# IO_V1_1.net
KiCad netlist of a schematic drawn in EAGLE
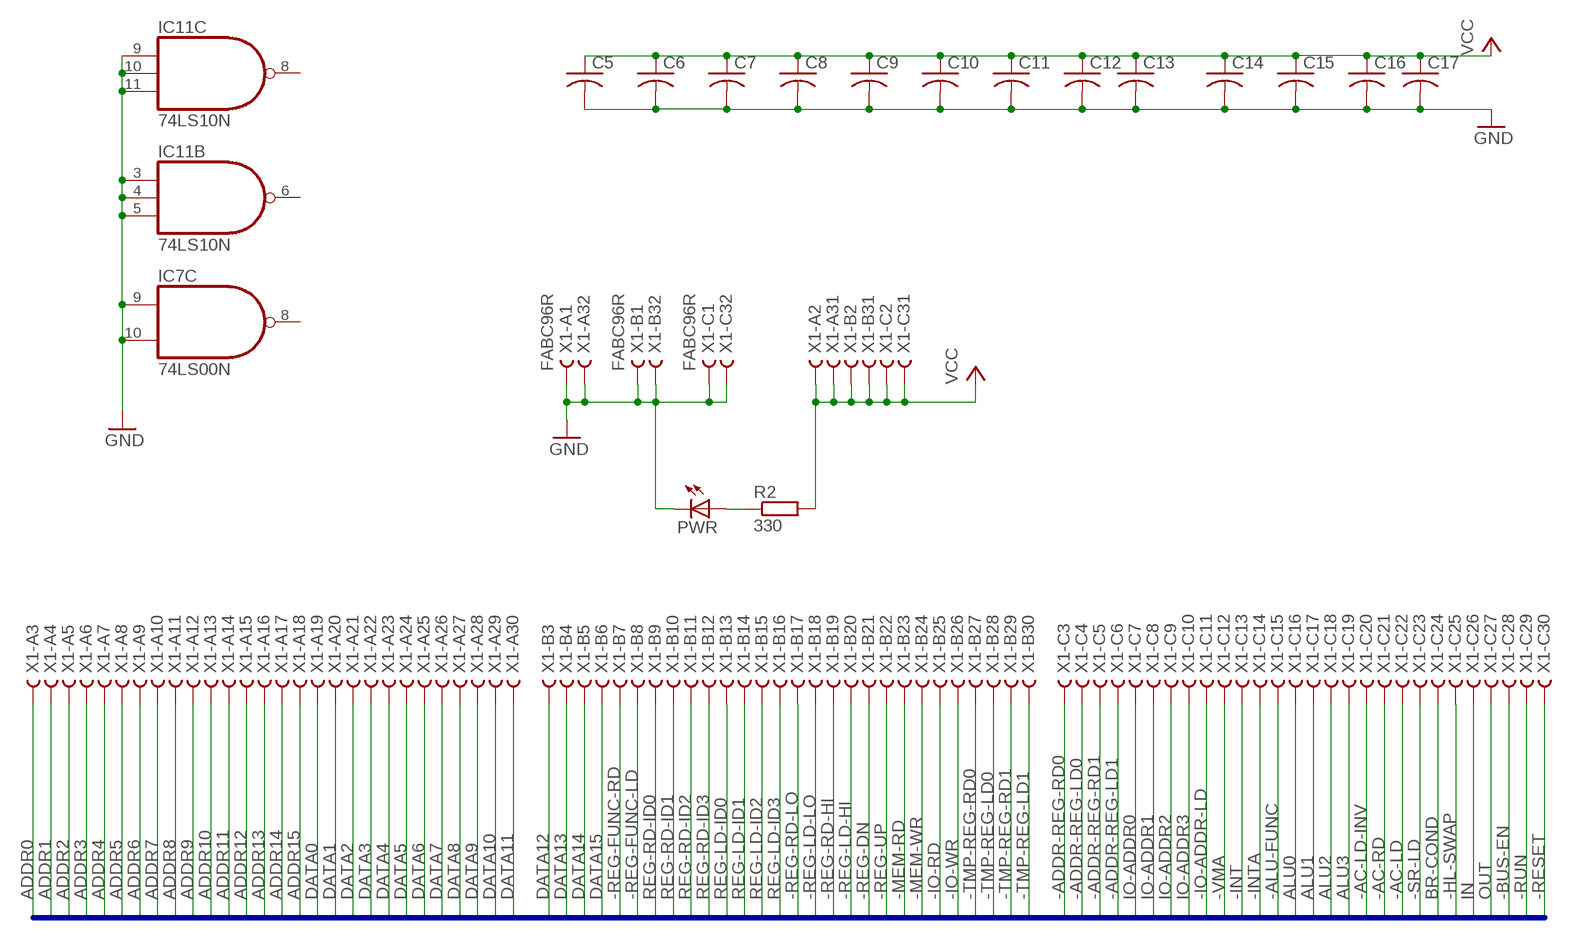
[diagram p0: schematic, sheet 1]
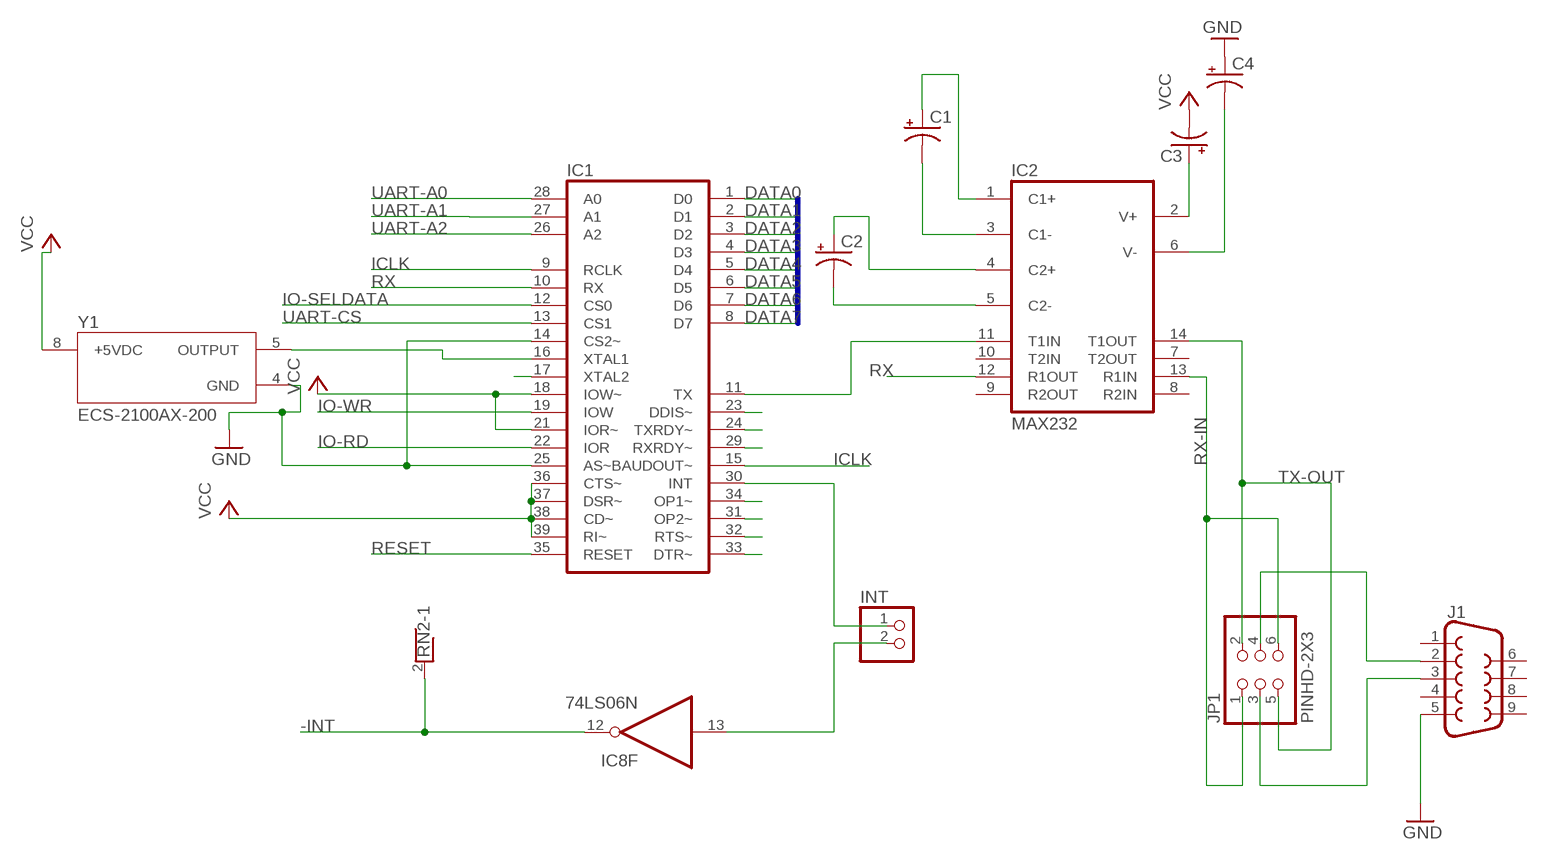
[diagram p1: schematic, sheet 2]
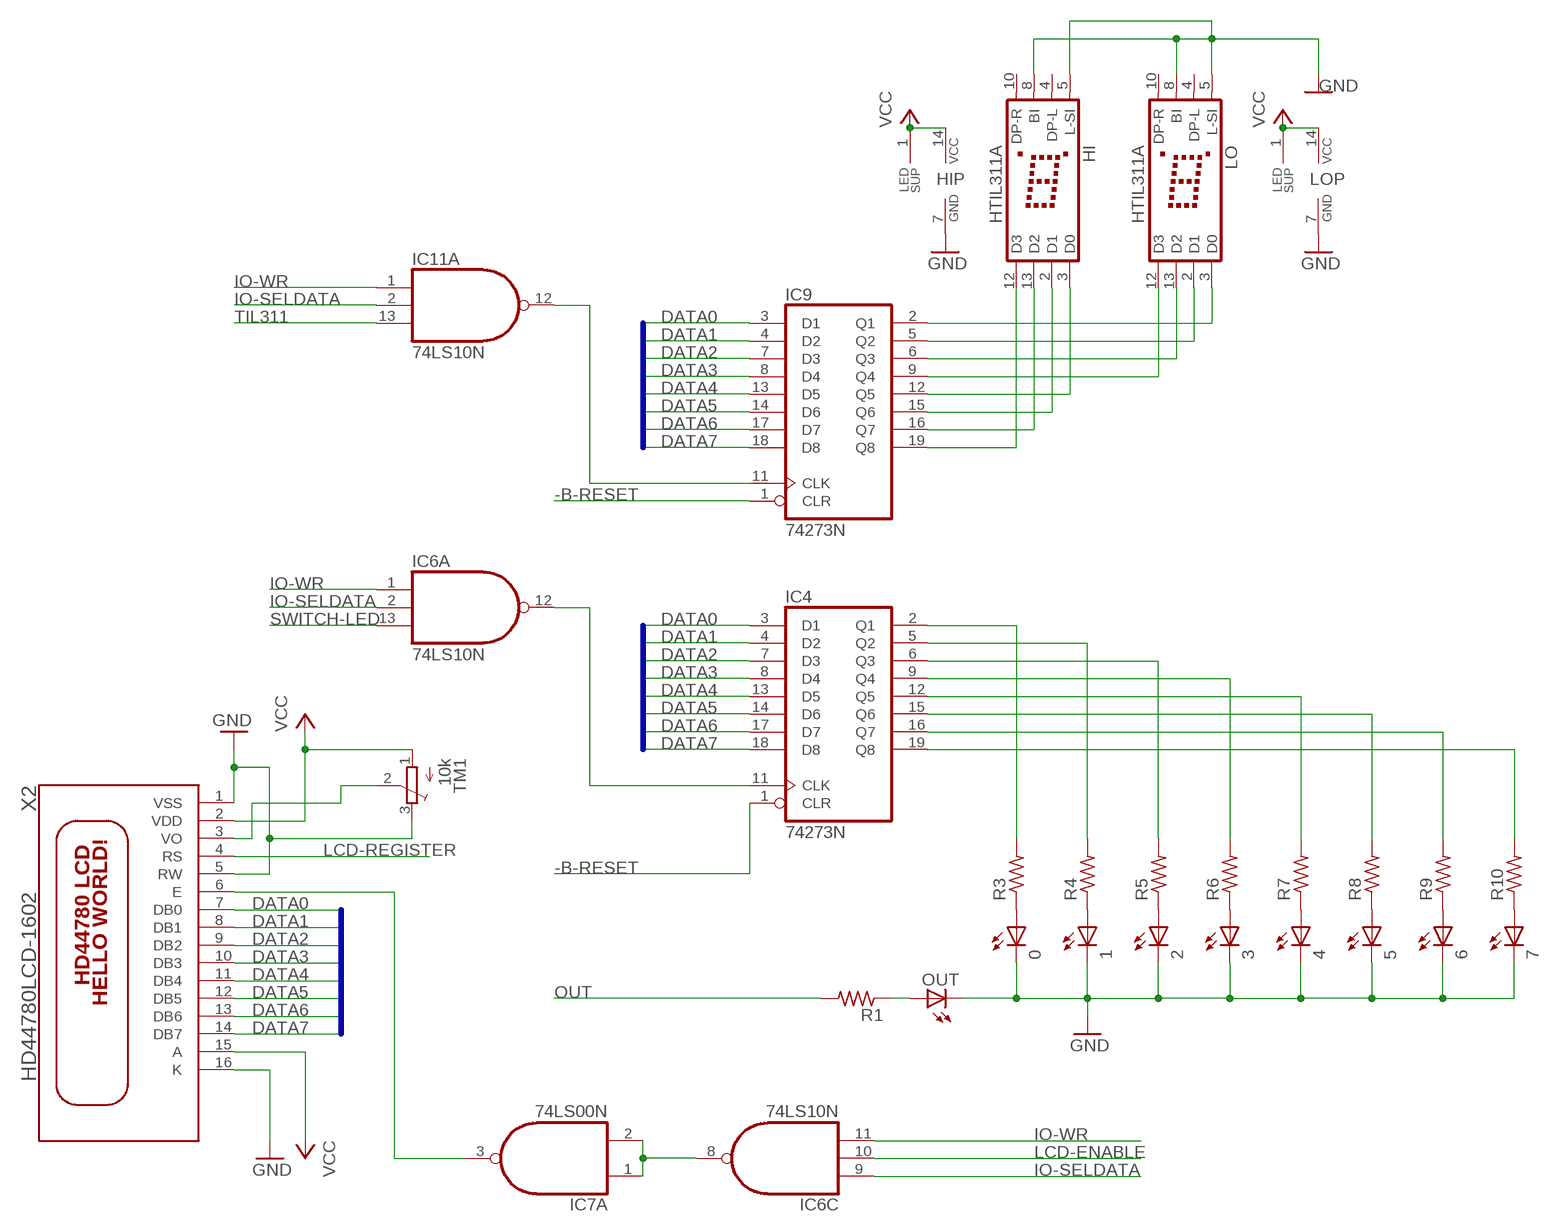
[diagram p2: schematic, sheet 3]
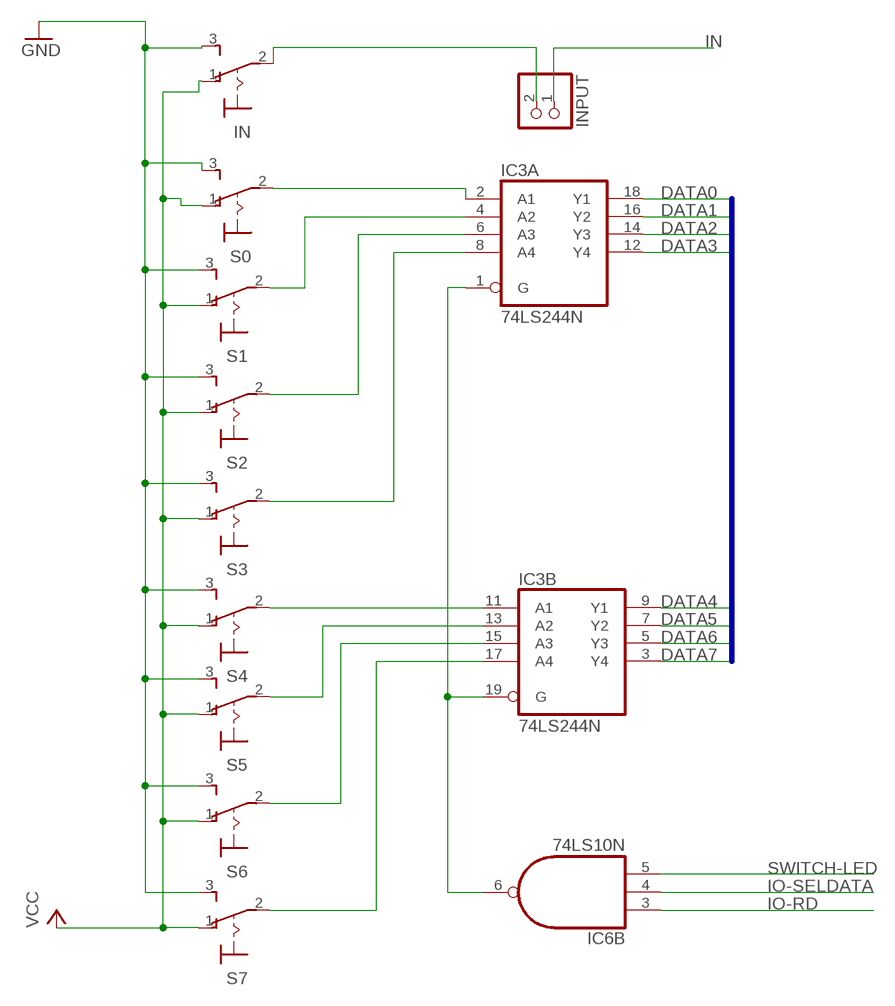
[diagram p3: schematic, sheet 4]
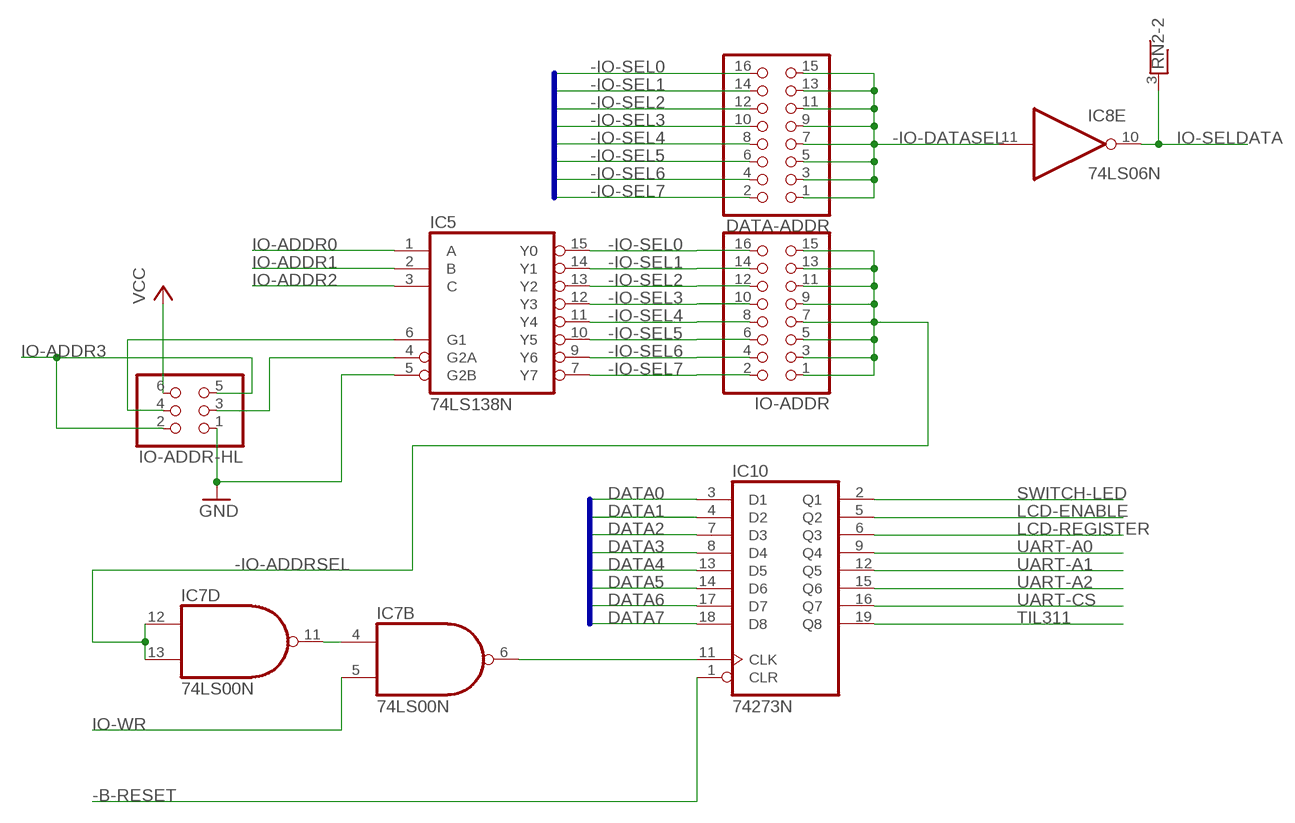
[diagram p4: schematic, sheet 5]
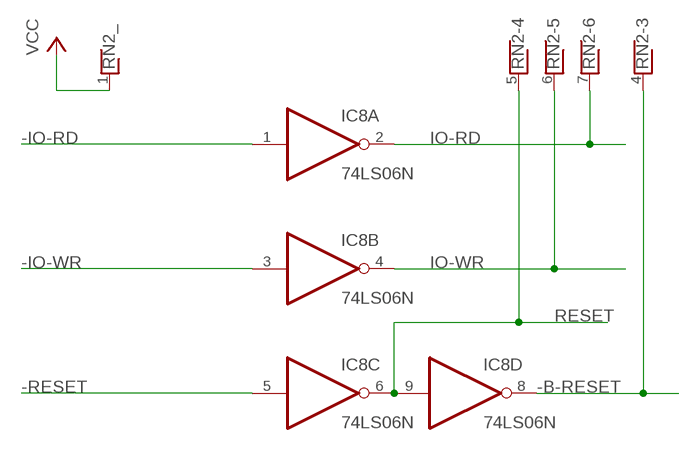
[diagram p5: schematic, sheet 6]

(export (version "E")
  (design (tool "Eeschema 10.0.6"))
  (components
    (comp (ref "C5")
      (value "C-US025-024X044")
      (footprint "eagle-import:C025-024X044")
      (libsource (lib "eagle-import") (part "C-US025-024X044"))
    )
    (comp (ref "C6")
      (value "C-US025-024X044")
      (footprint "eagle-import:C025-024X044")
      (libsource (lib "eagle-import") (part "C-US025-024X044"))
    )
    (comp (ref "C7")
      (value "C-US025-024X044")
      (footprint "eagle-import:C025-024X044")
      (libsource (lib "eagle-import") (part "C-US025-024X044"))
    )
    (comp (ref "C8")
      (value "C-US025-024X044")
      (footprint "eagle-import:C025-024X044")
      (libsource (lib "eagle-import") (part "C-US025-024X044"))
    )
    (comp (ref "C9")
      (value "C-US025-024X044")
      (footprint "eagle-import:C025-024X044")
      (libsource (lib "eagle-import") (part "C-US025-024X044"))
    )
    (comp (ref "C10")
      (value "C-US025-024X044")
      (footprint "eagle-import:C025-024X044")
      (libsource (lib "eagle-import") (part "C-US025-024X044"))
    )
    (comp (ref "C11")
      (value "C-US025-024X044")
      (footprint "eagle-import:C025-024X044")
      (libsource (lib "eagle-import") (part "C-US025-024X044"))
    )
    (comp (ref "C12")
      (value "C-US025-024X044")
      (footprint "eagle-import:C025-024X044")
      (libsource (lib "eagle-import") (part "C-US025-024X044"))
    )
    (comp (ref "C13")
      (value "C-US025-024X044")
      (footprint "eagle-import:C025-024X044")
      (libsource (lib "eagle-import") (part "C-US025-024X044"))
    )
    (comp (ref "C14")
      (value "C-US025-024X044")
      (footprint "eagle-import:C025-024X044")
      (libsource (lib "eagle-import") (part "C-US025-024X044"))
    )
    (comp (ref "C15")
      (value "C-US025-024X044")
      (footprint "eagle-import:C025-024X044")
      (libsource (lib "eagle-import") (part "C-US025-024X044"))
    )
    (comp (ref "C16")
      (value "C-US025-024X044")
      (footprint "eagle-import:C025-024X044")
      (libsource (lib "eagle-import") (part "C-US025-024X044"))
    )
    (comp (ref "C17")
      (value "C-US025-024X044")
      (footprint "eagle-import:C025-024X044")
      (libsource (lib "eagle-import") (part "C-US025-024X044"))
    )
    (comp (ref "IC7")
      (value "74LS00N")
      (footprint "eagle-import:DIL14")
      (libsource (lib "eagle-import") (part "7400NLS"))
    )
    (comp (ref "IC11")
      (value "74LS10N")
      (footprint "eagle-import:DIL14")
      (libsource (lib "eagle-import") (part "7410NLS"))
    )
    (comp (ref "PWR")
      (value "LED5MM")
      (footprint "eagle-import:LED5MM")
      (libsource (lib "eagle-import") (part "led_LED5MM"))
    )
    (comp (ref "R2")
      (value "330")
      (footprint "eagle-import:0207_10")
      (libsource (lib "eagle-import") (part "R0207/10"))
    )
    (comp (ref "X1")
      (value "FABC96R")
      (footprint "eagle-import:FABC96R")
      (libsource (lib "eagle-import") (part "FABC96R"))
    )
    (comp (ref "0")
      (value "LED5MM")
      (footprint "eagle-import:LED5MM")
      (libsource (lib "eagle-import") (part "LED5MM"))
    )
    (comp (ref "1")
      (value "LED5MM")
      (footprint "eagle-import:LED5MM")
      (libsource (lib "eagle-import") (part "LED5MM"))
    )
    (comp (ref "2")
      (value "LED5MM")
      (footprint "eagle-import:LED5MM")
      (libsource (lib "eagle-import") (part "LED5MM"))
    )
    (comp (ref "3")
      (value "LED5MM")
      (footprint "eagle-import:LED5MM")
      (libsource (lib "eagle-import") (part "LED5MM"))
    )
    (comp (ref "4")
      (value "LED5MM")
      (footprint "eagle-import:LED5MM")
      (libsource (lib "eagle-import") (part "LED5MM"))
    )
    (comp (ref "5")
      (value "LED5MM")
      (footprint "eagle-import:LED5MM")
      (libsource (lib "eagle-import") (part "LED5MM"))
    )
    (comp (ref "6")
      (value "LED5MM")
      (footprint "eagle-import:LED5MM")
      (libsource (lib "eagle-import") (part "LED5MM"))
    )
    (comp (ref "7")
      (value "LED5MM")
      (footprint "eagle-import:LED5MM")
      (libsource (lib "eagle-import") (part "LED5MM"))
    )
    (comp (ref "HI")
      (value "HTIL311A")
      (footprint "eagle-import:HTIL311A")
      (libsource (lib "eagle-import") (part "HTIL311A"))
    )
    (comp (ref "IC4")
      (value "74273N")
      (footprint "eagle-import:DIL20")
      (libsource (lib "eagle-import") (part "74273N"))
    )
    (comp (ref "IC6")
      (value "74LS10N")
      (footprint "eagle-import:DIL14")
      (libsource (lib "eagle-import") (part "7410NLS"))
    )
    (comp (ref "IC9")
      (value "74273N")
      (footprint "eagle-import:DIL20")
      (libsource (lib "eagle-import") (part "74273N"))
    )
    (comp (ref "LO")
      (value "HTIL311A")
      (footprint "eagle-import:HTIL311A")
      (libsource (lib "eagle-import") (part "HTIL311A"))
    )
    (comp (ref "OUT")
      (value "LED5MM")
      (footprint "eagle-import:LED5MM")
      (libsource (lib "eagle-import") (part "LED5MM"))
    )
    (comp (ref "R1")
      (value "R-US_0207/10")
      (footprint "eagle-import:0207_10")
      (libsource (lib "eagle-import") (part "R-US_0207/10"))
    )
    (comp (ref "R3")
      (value "R-US_0207/10")
      (footprint "eagle-import:0207_10")
      (libsource (lib "eagle-import") (part "R-US_0207/10"))
    )
    (comp (ref "R4")
      (value "R-US_0207/10")
      (footprint "eagle-import:0207_10")
      (libsource (lib "eagle-import") (part "R-US_0207/10"))
    )
    (comp (ref "R5")
      (value "R-US_0207/10")
      (footprint "eagle-import:0207_10")
      (libsource (lib "eagle-import") (part "R-US_0207/10"))
    )
    (comp (ref "R6")
      (value "R-US_0207/10")
      (footprint "eagle-import:0207_10")
      (libsource (lib "eagle-import") (part "R-US_0207/10"))
    )
    (comp (ref "R7")
      (value "R-US_0207/10")
      (footprint "eagle-import:0207_10")
      (libsource (lib "eagle-import") (part "R-US_0207/10"))
    )
    (comp (ref "R8")
      (value "R-US_0207/10")
      (footprint "eagle-import:0207_10")
      (libsource (lib "eagle-import") (part "R-US_0207/10"))
    )
    (comp (ref "R9")
      (value "R-US_0207/10")
      (footprint "eagle-import:0207_10")
      (libsource (lib "eagle-import") (part "R-US_0207/10"))
    )
    (comp (ref "R10")
      (value "R-US_0207/10")
      (footprint "eagle-import:0207_10")
      (libsource (lib "eagle-import") (part "R-US_0207/10"))
    )
    (comp (ref "TM1")
      (value "10k")
      (footprint "eagle-import:TRIM-3386")
      (libsource (lib "eagle-import") (part "TRIMPOT3386"))
    )
    (comp (ref "X2")
      (value "HD44780LCD-1602")
      (footprint "eagle-import:LCD1602")
      (libsource (lib "eagle-import") (part "HD44780LCD-1602"))
    )
    (comp (ref "DATA-ADDR")
      (value "PINHD-2X8")
      (footprint "eagle-import:2X08")
      (libsource (lib "eagle-import") (part "PINHD-2X8"))
    )
    (comp (ref "IC5")
      (value "74LS138N")
      (footprint "eagle-import:DIL16")
      (libsource (lib "eagle-import") (part "74138NLS"))
    )
    (comp (ref "IC8")
      (value "74LS06N")
      (footprint "eagle-import:DIL14")
      (libsource (lib "eagle-import") (part "7406NLS"))
    )
    (comp (ref "IC10")
      (value "74273N")
      (footprint "eagle-import:DIL20")
      (libsource (lib "eagle-import") (part "74273N"))
    )
    (comp (ref "IO-ADDR")
      (value "PINHD-2X8")
      (footprint "eagle-import:2X08")
      (libsource (lib "eagle-import") (part "PINHD-2X8"))
    )
    (comp (ref "IO-ADDR-HL")
      (value "PINHD-2X3")
      (footprint "eagle-import:2X03")
      (libsource (lib "eagle-import") (part "pinhead_325_PINHD-2X3"))
    )
    (comp (ref "RN2")
      (value "RNX6")
      (footprint "eagle-import:RN-7")
      (libsource (lib "eagle-import") (part "RNX6"))
    )
    (comp (ref "IC3")
      (value "74LS244N")
      (footprint "eagle-import:DIL20")
      (libsource (lib "eagle-import") (part "74xx-us_88_74244NLS"))
    )
    (comp (ref "IN")
      (value "M9040P")
      (footprint "eagle-import:M9040P")
      (libsource (lib "eagle-import") (part "M9040P"))
    )
    (comp (ref "INPUT")
      (value "PINHD-1X2")
      (footprint "eagle-import:1X02")
      (libsource (lib "eagle-import") (part "PINHD-1X2"))
    )
    (comp (ref "S0")
      (value "M9040P")
      (footprint "eagle-import:M9040P")
      (libsource (lib "eagle-import") (part "M9040P"))
    )
    (comp (ref "S1")
      (value "M9040P")
      (footprint "eagle-import:M9040P")
      (libsource (lib "eagle-import") (part "M9040P"))
    )
    (comp (ref "S2")
      (value "M9040P")
      (footprint "eagle-import:M9040P")
      (libsource (lib "eagle-import") (part "M9040P"))
    )
    (comp (ref "S3")
      (value "M9040P")
      (footprint "eagle-import:M9040P")
      (libsource (lib "eagle-import") (part "M9040P"))
    )
    (comp (ref "S4")
      (value "M9040P")
      (footprint "eagle-import:M9040P")
      (libsource (lib "eagle-import") (part "M9040P"))
    )
    (comp (ref "S5")
      (value "M9040P")
      (footprint "eagle-import:M9040P")
      (libsource (lib "eagle-import") (part "M9040P"))
    )
    (comp (ref "S6")
      (value "M9040P")
      (footprint "eagle-import:M9040P")
      (libsource (lib "eagle-import") (part "M9040P"))
    )
    (comp (ref "S7")
      (value "M9040P")
      (footprint "eagle-import:M9040P")
      (libsource (lib "eagle-import") (part "M9040P"))
    )
    (comp (ref "C1")
      (value "CPOL-USE2,5-6E")
      (footprint "eagle-import:E2,5-6E")
      (libsource (lib "eagle-import") (part "CPOL-USE2,5-6E"))
    )
    (comp (ref "C2")
      (value "CPOL-USE2,5-6E")
      (footprint "eagle-import:E2,5-6E")
      (libsource (lib "eagle-import") (part "CPOL-USE2,5-6E"))
    )
    (comp (ref "C3")
      (value "CPOL-USE2,5-6E")
      (footprint "eagle-import:E2,5-6E")
      (libsource (lib "eagle-import") (part "CPOL-USE2,5-6E"))
    )
    (comp (ref "C4")
      (value "CPOL-USE2,5-6E")
      (footprint "eagle-import:E2,5-6E")
      (libsource (lib "eagle-import") (part "CPOL-USE2,5-6E"))
    )
    (comp (ref "IC1")
      (value "XR-16C550P")
      (footprint "eagle-import:DIL40")
      (fields (field (name "MPN") "ST16C450CP40"))
      (libsource (lib "eagle-import") (part "XR-16C550P"))
    )
    (comp (ref "IC2")
      (value "MAX232")
      (footprint "eagle-import:DIL16")
      (fields (field (name "MF") "MAXIM") (field (name "MPN") "MAX232ACPE+"))
      (libsource (lib "eagle-import") (part "MAX232"))
    )
    (comp (ref "INT")
      (value "PINHD-1X2")
      (footprint "eagle-import:1X02")
      (libsource (lib "eagle-import") (part "PINHD-1X2"))
    )
    (comp (ref "J1")
      (value "DB9FEMALE")
      (footprint "eagle-import:DB9")
      (libsource (lib "eagle-import") (part "DB9FEMALE"))
    )
    (comp (ref "JP1")
      (value "PINHD-2X3")
      (footprint "eagle-import:2X03")
      (libsource (lib "eagle-import") (part "PINHD-2X3"))
    )
    (comp (ref "Y1")
      (value "ECS-2100AX-200")
      (footprint "eagle-import:ECS-2100AX-200")
      (fields
        (field (name "DIGIKEY_PART_NUMBER") "X964-ND")
        (field (name "MANUFACTURER") "ECS Inc.")
        (field (name "CREATED_BY") "PCBLayout.com")
      )
      (libsource (lib "eagle-import") (part "ECS-2100AX-200"))
    )
  )
  (nets
    (net (code "1") (name "-AC-LD") (class "Default")
      (node (ref "X1") (pin "C22") (pinfunction "B_C22") (pintype "passive"))
    )
    (net (code "2") (name "-AC-LD-INV") (class "Default")
      (node (ref "X1") (pin "C20") (pinfunction "B_C20") (pintype "passive"))
    )
    (net (code "3") (name "-AC-RD") (class "Default")
      (node (ref "X1") (pin "C21") (pinfunction "B_C21") (pintype "passive"))
    )
    (net (code "4") (name "-ADDR-REG-LD0") (class "Default")
      (node (ref "X1") (pin "C4") (pinfunction "B_C4") (pintype "passive"))
    )
    (net (code "5") (name "-ADDR-REG-LD1") (class "Default")
      (node (ref "X1") (pin "C6") (pinfunction "B_C6") (pintype "passive"))
    )
    (net (code "6") (name "-ADDR-REG-RD0") (class "Default")
      (node (ref "X1") (pin "C3") (pinfunction "B_C3") (pintype "passive"))
    )
    (net (code "7") (name "-ADDR-REG-RD1") (class "Default")
      (node (ref "X1") (pin "C5") (pinfunction "B_C5") (pintype "passive"))
    )
    (net (code "8") (name "-ALU-FUNC") (class "Default")
      (node (ref "X1") (pin "C15") (pinfunction "B_C15") (pintype "passive"))
    )
    (net (code "9") (name "-B-RESET") (class "Default")
      (node (ref "IC10") (pin "1") (pinfunction "CLR_1") (pintype "input"))
      (node (ref "IC4") (pin "1") (pinfunction "CLR_1") (pintype "input"))
      (node (ref "IC8") (pin "8") (pinfunction "O_8") (pintype "open_collector"))
      (node (ref "IC9") (pin "1") (pinfunction "CLR_1") (pintype "input"))
      (node (ref "RN2") (pin "4") (pinfunction "1_4") (pintype "passive"))
    )
    (net (code "10") (name "-BUS-EN") (class "Default")
      (node (ref "X1") (pin "C28") (pinfunction "B_C28") (pintype "passive"))
    )
    (net (code "11") (name "-HL-SWAP") (class "Default")
      (node (ref "X1") (pin "C25") (pinfunction "B_C25") (pintype "passive"))
    )
    (net (code "12") (name "-INT") (class "Default")
      (node (ref "IC8") (pin "12") (pinfunction "O_12") (pintype "open_collector"))
      (node (ref "RN2") (pin "2") (pinfunction "1_2") (pintype "passive"))
      (node (ref "X1") (pin "C13") (pinfunction "B_C13") (pintype "passive"))
    )
    (net (code "13") (name "-INTA") (class "Default")
      (node (ref "X1") (pin "C14") (pinfunction "B_C14") (pintype "passive"))
    )
    (net (code "14") (name "-IO-ADDR-LD") (class "Default")
      (node (ref "X1") (pin "C11") (pinfunction "B_C11") (pintype "passive"))
    )
    (net (code "15") (name "-IO-ADDRSEL") (class "Default")
      (node (ref "IC7") (pin "12") (pinfunction "I0_12") (pintype "input"))
      (node (ref "IC7") (pin "13") (pinfunction "I1_13") (pintype "input"))
      (node (ref "IO-ADDR") (pin "1") (pinfunction "1_1") (pintype "passive"))
      (node (ref "IO-ADDR") (pin "11") (pinfunction "11_11") (pintype "passive"))
      (node (ref "IO-ADDR") (pin "13") (pinfunction "13_13") (pintype "passive"))
      (node (ref "IO-ADDR") (pin "15") (pinfunction "15_15") (pintype "passive"))
      (node (ref "IO-ADDR") (pin "3") (pinfunction "3_3") (pintype "passive"))
      (node (ref "IO-ADDR") (pin "5") (pinfunction "5_5") (pintype "passive"))
      (node (ref "IO-ADDR") (pin "7") (pinfunction "7_7") (pintype "passive"))
      (node (ref "IO-ADDR") (pin "9") (pinfunction "9_9") (pintype "passive"))
    )
    (net (code "16") (name "-IO-DATASEL") (class "Default")
      (node (ref "DATA-ADDR") (pin "1") (pinfunction "1_1") (pintype "passive"))
      (node (ref "DATA-ADDR") (pin "11") (pinfunction "11_11") (pintype "passive"))
      (node (ref "DATA-ADDR") (pin "13") (pinfunction "13_13") (pintype "passive"))
      (node (ref "DATA-ADDR") (pin "15") (pinfunction "15_15") (pintype "passive"))
      (node (ref "DATA-ADDR") (pin "3") (pinfunction "3_3") (pintype "passive"))
      (node (ref "DATA-ADDR") (pin "5") (pinfunction "5_5") (pintype "passive"))
      (node (ref "DATA-ADDR") (pin "7") (pinfunction "7_7") (pintype "passive"))
      (node (ref "DATA-ADDR") (pin "9") (pinfunction "9_9") (pintype "passive"))
      (node (ref "IC8") (pin "11") (pinfunction "I_11") (pintype "input"))
    )
    (net (code "17") (name "-IO-RD") (class "Default")
      (node (ref "IC8") (pin "1") (pinfunction "I_1") (pintype "input"))
      (node (ref "X1") (pin "B25") (pinfunction "B_B25") (pintype "passive"))
    )
    (net (code "18") (name "-IO-SEL0") (class "Default")
      (node (ref "DATA-ADDR") (pin "16") (pinfunction "16_16") (pintype "passive"))
      (node (ref "IC5") (pin "15") (pinfunction "Y0_15") (pintype "output"))
      (node (ref "IO-ADDR") (pin "16") (pinfunction "16_16") (pintype "passive"))
    )
    (net (code "19") (name "-IO-SEL1") (class "Default")
      (node (ref "DATA-ADDR") (pin "14") (pinfunction "14_14") (pintype "passive"))
      (node (ref "IC5") (pin "14") (pinfunction "Y1_14") (pintype "output"))
      (node (ref "IO-ADDR") (pin "14") (pinfunction "14_14") (pintype "passive"))
    )
    (net (code "20") (name "-IO-SEL2") (class "Default")
      (node (ref "DATA-ADDR") (pin "12") (pinfunction "12_12") (pintype "passive"))
      (node (ref "IC5") (pin "13") (pinfunction "Y2_13") (pintype "output"))
      (node (ref "IO-ADDR") (pin "12") (pinfunction "12_12") (pintype "passive"))
    )
    (net (code "21") (name "-IO-SEL3") (class "Default")
      (node (ref "DATA-ADDR") (pin "10") (pinfunction "10_10") (pintype "passive"))
      (node (ref "IC5") (pin "12") (pinfunction "Y3_12") (pintype "output"))
      (node (ref "IO-ADDR") (pin "10") (pinfunction "10_10") (pintype "passive"))
    )
    (net (code "22") (name "-IO-SEL4") (class "Default")
      (node (ref "DATA-ADDR") (pin "8") (pinfunction "8_8") (pintype "passive"))
      (node (ref "IC5") (pin "11") (pinfunction "Y4_11") (pintype "output"))
      (node (ref "IO-ADDR") (pin "8") (pinfunction "8_8") (pintype "passive"))
    )
    (net (code "23") (name "-IO-SEL5") (class "Default")
      (node (ref "DATA-ADDR") (pin "6") (pinfunction "6_6") (pintype "passive"))
      (node (ref "IC5") (pin "10") (pinfunction "Y5_10") (pintype "output"))
      (node (ref "IO-ADDR") (pin "6") (pinfunction "6_6") (pintype "passive"))
    )
    (net (code "24") (name "-IO-SEL6") (class "Default")
      (node (ref "DATA-ADDR") (pin "4") (pinfunction "4_4") (pintype "passive"))
      (node (ref "IC5") (pin "9") (pinfunction "Y6_9") (pintype "output"))
      (node (ref "IO-ADDR") (pin "4") (pinfunction "4_4") (pintype "passive"))
    )
    (net (code "25") (name "-IO-SEL7") (class "Default")
      (node (ref "DATA-ADDR") (pin "2") (pinfunction "2_2") (pintype "passive"))
      (node (ref "IC5") (pin "7") (pinfunction "Y7_7") (pintype "output"))
      (node (ref "IO-ADDR") (pin "2") (pinfunction "2_2") (pintype "passive"))
    )
    (net (code "26") (name "-IO-WR") (class "Default")
      (node (ref "IC8") (pin "3") (pinfunction "I_3") (pintype "input"))
      (node (ref "X1") (pin "B26") (pinfunction "B_B26") (pintype "passive"))
    )
    (net (code "27") (name "-MEM-RD") (class "Default")
      (node (ref "X1") (pin "B23") (pinfunction "B_B23") (pintype "passive"))
    )
    (net (code "28") (name "-MEM-WR") (class "Default")
      (node (ref "X1") (pin "B24") (pinfunction "B_B24") (pintype "passive"))
    )
    (net (code "29") (name "-REG-DN") (class "Default")
      (node (ref "X1") (pin "B21") (pinfunction "B_B21") (pintype "passive"))
    )
    (net (code "30") (name "-REG-FUNC-LD") (class "Default")
      (node (ref "X1") (pin "B8") (pinfunction "B_B8") (pintype "passive"))
    )
    (net (code "31") (name "-REG-FUNC-RD") (class "Default")
      (node (ref "X1") (pin "B7") (pinfunction "B_B7") (pintype "passive"))
    )
    (net (code "32") (name "-REG-LD-HI") (class "Default")
      (node (ref "X1") (pin "B20") (pinfunction "B_B20") (pintype "passive"))
    )
    (net (code "33") (name "-REG-LD-LO") (class "Default")
      (node (ref "X1") (pin "B18") (pinfunction "B_B18") (pintype "passive"))
    )
    (net (code "34") (name "-REG-RD-HI") (class "Default")
      (node (ref "X1") (pin "B19") (pinfunction "B_B19") (pintype "passive"))
    )
    (net (code "35") (name "-REG-RD-LO") (class "Default")
      (node (ref "X1") (pin "B17") (pinfunction "B_B17") (pintype "passive"))
    )
    (net (code "36") (name "-REG-UP") (class "Default")
      (node (ref "X1") (pin "B22") (pinfunction "B_B22") (pintype "passive"))
    )
    (net (code "37") (name "-RESET") (class "Default")
      (node (ref "IC8") (pin "5") (pinfunction "I_5") (pintype "input"))
      (node (ref "X1") (pin "C30") (pinfunction "B_C30") (pintype "passive"))
    )
    (net (code "38") (name "-RUN") (class "Default")
      (node (ref "X1") (pin "C29") (pinfunction "B_C29") (pintype "passive"))
    )
    (net (code "39") (name "-SR-LD") (class "Default")
      (node (ref "X1") (pin "C23") (pinfunction "B_C23") (pintype "passive"))
    )
    (net (code "40") (name "-TMP-REG-LD0") (class "Default")
      (node (ref "X1") (pin "B28") (pinfunction "B_B28") (pintype "passive"))
    )
    (net (code "41") (name "-TMP-REG-LD1") (class "Default")
      (node (ref "X1") (pin "B30") (pinfunction "B_B30") (pintype "passive"))
    )
    (net (code "42") (name "-TMP-REG-RD0") (class "Default")
      (node (ref "X1") (pin "B27") (pinfunction "B_B27") (pintype "passive"))
    )
    (net (code "43") (name "-TMP-REG-RD1") (class "Default")
      (node (ref "X1") (pin "B29") (pinfunction "B_B29") (pintype "passive"))
    )
    (net (code "44") (name "-VMA") (class "Default")
      (node (ref "X1") (pin "C12") (pinfunction "B_C12") (pintype "passive"))
    )
    (net (code "45") (name "ADDR0") (class "Default")
      (node (ref "X1") (pin "A3") (pinfunction "B_A3") (pintype "passive"))
    )
    (net (code "46") (name "ADDR1") (class "Default")
      (node (ref "X1") (pin "A4") (pinfunction "B_A4") (pintype "passive"))
    )
    (net (code "47") (name "ADDR2") (class "Default")
      (node (ref "X1") (pin "A5") (pinfunction "B_A5") (pintype "passive"))
    )
    (net (code "48") (name "ADDR3") (class "Default")
      (node (ref "X1") (pin "A6") (pinfunction "B_A6") (pintype "passive"))
    )
    (net (code "49") (name "ADDR4") (class "Default")
      (node (ref "X1") (pin "A7") (pinfunction "B_A7") (pintype "passive"))
    )
    (net (code "50") (name "ADDR5") (class "Default")
      (node (ref "X1") (pin "A8") (pinfunction "B_A8") (pintype "passive"))
    )
    (net (code "51") (name "ADDR6") (class "Default")
      (node (ref "X1") (pin "A9") (pinfunction "B_A9") (pintype "passive"))
    )
    (net (code "52") (name "ADDR7") (class "Default")
      (node (ref "X1") (pin "A10") (pinfunction "B_A10") (pintype "passive"))
    )
    (net (code "53") (name "ADDR8") (class "Default")
      (node (ref "X1") (pin "A11") (pinfunction "B_A11") (pintype "passive"))
    )
    (net (code "54") (name "ADDR9") (class "Default")
      (node (ref "X1") (pin "A12") (pinfunction "B_A12") (pintype "passive"))
    )
    (net (code "55") (name "ADDR10") (class "Default")
      (node (ref "X1") (pin "A13") (pinfunction "B_A13") (pintype "passive"))
    )
    (net (code "56") (name "ADDR11") (class "Default")
      (node (ref "X1") (pin "A14") (pinfunction "B_A14") (pintype "passive"))
    )
    (net (code "57") (name "ADDR12") (class "Default")
      (node (ref "X1") (pin "A15") (pinfunction "B_A15") (pintype "passive"))
    )
    (net (code "58") (name "ADDR13") (class "Default")
      (node (ref "X1") (pin "A16") (pinfunction "B_A16") (pintype "passive"))
    )
    (net (code "59") (name "ADDR14") (class "Default")
      (node (ref "X1") (pin "A17") (pinfunction "B_A17") (pintype "passive"))
    )
    (net (code "60") (name "ADDR15") (class "Default")
      (node (ref "X1") (pin "A18") (pinfunction "B_A18") (pintype "passive"))
    )
    (net (code "61") (name "ALU0") (class "Default")
      (node (ref "X1") (pin "C16") (pinfunction "B_C16") (pintype "passive"))
    )
    (net (code "62") (name "ALU1") (class "Default")
      (node (ref "X1") (pin "C17") (pinfunction "B_C17") (pintype "passive"))
    )
    (net (code "63") (name "ALU2") (class "Default")
      (node (ref "X1") (pin "C18") (pinfunction "B_C18") (pintype "passive"))
    )
    (net (code "64") (name "ALU3") (class "Default")
      (node (ref "X1") (pin "C19") (pinfunction "B_C19") (pintype "passive"))
    )
    (net (code "65") (name "BR-COND") (class "Default")
      (node (ref "X1") (pin "C24") (pinfunction "B_C24") (pintype "passive"))
    )
    (net (code "66") (name "DATA0") (class "Default")
      (node (ref "IC1") (pin "1") (pinfunction "D0_1") (pintype "bidirectional"))
      (node (ref "IC10") (pin "3") (pinfunction "D1_3") (pintype "input"))
      (node (ref "IC3") (pin "18") (pinfunction "Y1_18") (pintype "tri_state"))
      (node (ref "IC4") (pin "3") (pinfunction "D1_3") (pintype "input"))
      (node (ref "IC9") (pin "3") (pinfunction "D1_3") (pintype "input"))
      (node (ref "X1") (pin "A19") (pinfunction "B_A19") (pintype "passive"))
      (node (ref "X2") (pin "7") (pinfunction "DB0_7") (pintype "bidirectional"))
    )
    (net (code "67") (name "DATA1") (class "Default")
      (node (ref "IC1") (pin "2") (pinfunction "D1_2") (pintype "bidirectional"))
      (node (ref "IC10") (pin "4") (pinfunction "D2_4") (pintype "input"))
      (node (ref "IC3") (pin "16") (pinfunction "Y2_16") (pintype "tri_state"))
      (node (ref "IC4") (pin "4") (pinfunction "D2_4") (pintype "input"))
      (node (ref "IC9") (pin "4") (pinfunction "D2_4") (pintype "input"))
      (node (ref "X1") (pin "A20") (pinfunction "B_A20") (pintype "passive"))
      (node (ref "X2") (pin "8") (pinfunction "DB1_8") (pintype "bidirectional"))
    )
    (net (code "68") (name "DATA2") (class "Default")
      (node (ref "IC1") (pin "3") (pinfunction "D2_3") (pintype "bidirectional"))
      (node (ref "IC10") (pin "7") (pinfunction "D3_7") (pintype "input"))
      (node (ref "IC3") (pin "14") (pinfunction "Y3_14") (pintype "tri_state"))
      (node (ref "IC4") (pin "7") (pinfunction "D3_7") (pintype "input"))
      (node (ref "IC9") (pin "7") (pinfunction "D3_7") (pintype "input"))
      (node (ref "X1") (pin "A21") (pinfunction "B_A21") (pintype "passive"))
      (node (ref "X2") (pin "9") (pinfunction "DB2_9") (pintype "bidirectional"))
    )
    (net (code "69") (name "DATA3") (class "Default")
      (node (ref "IC1") (pin "4") (pinfunction "D3_4") (pintype "bidirectional"))
      (node (ref "IC10") (pin "8") (pinfunction "D4_8") (pintype "input"))
      (node (ref "IC3") (pin "12") (pinfunction "Y4_12") (pintype "tri_state"))
      (node (ref "IC4") (pin "8") (pinfunction "D4_8") (pintype "input"))
      (node (ref "IC9") (pin "8") (pinfunction "D4_8") (pintype "input"))
      (node (ref "X1") (pin "A22") (pinfunction "B_A22") (pintype "passive"))
      (node (ref "X2") (pin "10") (pinfunction "DB3_10") (pintype "bidirectional"))
    )
    (net (code "70") (name "DATA4") (class "Default")
      (node (ref "IC1") (pin "5") (pinfunction "D4_5") (pintype "bidirectional"))
      (node (ref "IC10") (pin "13") (pinfunction "D5_13") (pintype "input"))
      (node (ref "IC3") (pin "9") (pinfunction "Y1_9") (pintype "tri_state"))
      (node (ref "IC4") (pin "13") (pinfunction "D5_13") (pintype "input"))
      (node (ref "IC9") (pin "13") (pinfunction "D5_13") (pintype "input"))
      (node (ref "X1") (pin "A23") (pinfunction "B_A23") (pintype "passive"))
      (node (ref "X2") (pin "11") (pinfunction "DB4_11") (pintype "bidirectional"))
    )
    (net (code "71") (name "DATA5") (class "Default")
      (node (ref "IC1") (pin "6") (pinfunction "D5_6") (pintype "bidirectional"))
      (node (ref "IC10") (pin "14") (pinfunction "D6_14") (pintype "input"))
      (node (ref "IC3") (pin "7") (pinfunction "Y2_7") (pintype "tri_state"))
      (node (ref "IC4") (pin "14") (pinfunction "D6_14") (pintype "input"))
      (node (ref "IC9") (pin "14") (pinfunction "D6_14") (pintype "input"))
      (node (ref "X1") (pin "A24") (pinfunction "B_A24") (pintype "passive"))
      (node (ref "X2") (pin "12") (pinfunction "DB5_12") (pintype "bidirectional"))
    )
    (net (code "72") (name "DATA6") (class "Default")
      (node (ref "IC1") (pin "7") (pinfunction "D6_7") (pintype "bidirectional"))
      (node (ref "IC10") (pin "17") (pinfunction "D7_17") (pintype "input"))
      (node (ref "IC3") (pin "5") (pinfunction "Y3_5") (pintype "tri_state"))
      (node (ref "IC4") (pin "17") (pinfunction "D7_17") (pintype "input"))
      (node (ref "IC9") (pin "17") (pinfunction "D7_17") (pintype "input"))
      (node (ref "X1") (pin "A25") (pinfunction "B_A25") (pintype "passive"))
      (node (ref "X2") (pin "13") (pinfunction "DB6_13") (pintype "bidirectional"))
    )
    (net (code "73") (name "DATA7") (class "Default")
      (node (ref "IC1") (pin "8") (pinfunction "D7_8") (pintype "bidirectional"))
      (node (ref "IC10") (pin "18") (pinfunction "D8_18") (pintype "input"))
      (node (ref "IC3") (pin "3") (pinfunction "Y4_3") (pintype "tri_state"))
      (node (ref "IC4") (pin "18") (pinfunction "D8_18") (pintype "input"))
      (node (ref "IC9") (pin "18") (pinfunction "D8_18") (pintype "input"))
      (node (ref "X1") (pin "A26") (pinfunction "B_A26") (pintype "passive"))
      (node (ref "X2") (pin "14") (pinfunction "DB7_14") (pintype "bidirectional"))
    )
    (net (code "74") (name "DATA8") (class "Default")
      (node (ref "X1") (pin "A27") (pinfunction "B_A27") (pintype "passive"))
    )
    (net (code "75") (name "DATA9") (class "Default")
      (node (ref "X1") (pin "A28") (pinfunction "B_A28") (pintype "passive"))
    )
    (net (code "76") (name "DATA10") (class "Default")
      (node (ref "X1") (pin "A29") (pinfunction "B_A29") (pintype "passive"))
    )
    (net (code "77") (name "DATA11") (class "Default")
      (node (ref "X1") (pin "A30") (pinfunction "B_A30") (pintype "passive"))
    )
    (net (code "78") (name "DATA12") (class "Default")
      (node (ref "X1") (pin "B3") (pinfunction "B_B3") (pintype "passive"))
    )
    (net (code "79") (name "DATA13") (class "Default")
      (node (ref "X1") (pin "B4") (pinfunction "B_B4") (pintype "passive"))
    )
    (net (code "80") (name "DATA14") (class "Default")
      (node (ref "X1") (pin "B5") (pinfunction "B_B5") (pintype "passive"))
    )
    (net (code "81") (name "DATA15") (class "Default")
      (node (ref "X1") (pin "B6") (pinfunction "B_B6") (pintype "passive"))
    )
    (net (code "82") (name "GND") (class "Default")
      (node (ref "0") (pin "K") (pinfunction "C_K") (pintype "passive"))
      (node (ref "1") (pin "K") (pinfunction "C_K") (pintype "passive"))
      (node (ref "2") (pin "K") (pinfunction "C_K") (pintype "passive"))
      (node (ref "3") (pin "K") (pinfunction "C_K") (pintype "passive"))
      (node (ref "4") (pin "K") (pinfunction "C_K") (pintype "passive"))
      (node (ref "5") (pin "K") (pinfunction "C_K") (pintype "passive"))
      (node (ref "6") (pin "K") (pinfunction "C_K") (pintype "passive"))
      (node (ref "7") (pin "K") (pinfunction "C_K") (pintype "passive"))
      (node (ref "C10") (pin "2") (pinfunction "2_2") (pintype "passive"))
      (node (ref "C11") (pin "2") (pinfunction "2_2") (pintype "passive"))
      (node (ref "C12") (pin "2") (pinfunction "2_2") (pintype "passive"))
      (node (ref "C13") (pin "2") (pinfunction "2_2") (pintype "passive"))
      (node (ref "C14") (pin "2") (pinfunction "2_2") (pintype "passive"))
      (node (ref "C15") (pin "2") (pinfunction "2_2") (pintype "passive"))
      (node (ref "C16") (pin "2") (pinfunction "2_2") (pintype "passive"))
      (node (ref "C17") (pin "2") (pinfunction "2_2") (pintype "passive"))
      (node (ref "C4") (pin "+") (pinfunction "+_+") (pintype "passive"))
      (node (ref "C5") (pin "2") (pinfunction "2_2") (pintype "passive"))
      (node (ref "C6") (pin "2") (pinfunction "2_2") (pintype "passive"))
      (node (ref "C7") (pin "2") (pinfunction "2_2") (pintype "passive"))
      (node (ref "C8") (pin "2") (pinfunction "2_2") (pintype "passive"))
      (node (ref "C9") (pin "2") (pinfunction "2_2") (pintype "passive"))
      (node (ref "HI") (pin "5") (pinfunction "L-SI_5") (pintype "input"))
      (node (ref "HI") (pin "7") (pinfunction "GND_7") (pintype "power_in"))
      (node (ref "HI") (pin "8") (pinfunction "BI_8") (pintype "input"))
      (node (ref "IC1") (pin "14") (pinfunction "CS2~{}_14") (pintype "input"))
      (node (ref "IC1") (pin "25") (pinfunction "AS~{}_25") (pintype "input"))
      (node (ref "IC11") (pin "10") (pinfunction "I1_10") (pintype "input"))
      (node (ref "IC11") (pin "11") (pinfunction "I2_11") (pintype "input"))
      (node (ref "IC11") (pin "3") (pinfunction "I0_3") (pintype "input"))
      (node (ref "IC11") (pin "4") (pinfunction "I1_4") (pintype "input"))
      (node (ref "IC11") (pin "5") (pinfunction "I2_5") (pintype "input"))
      (node (ref "IC11") (pin "9") (pinfunction "I0_9") (pintype "input"))
      (node (ref "IC5") (pin "5") (pinfunction "G2B_5") (pintype "input"))
      (node (ref "IC7") (pin "10") (pinfunction "I1_10") (pintype "input"))
      (node (ref "IC7") (pin "9") (pinfunction "I0_9") (pintype "input"))
      (node (ref "IN") (pin "3") (pinfunction "S_3") (pintype "passive"))
      (node (ref "IO-ADDR-HL") (pin "1") (pinfunction "1_1") (pintype "passive"))
      (node (ref "J1") (pin "5") (pinfunction "5_5") (pintype "passive"))
      (node (ref "LO") (pin "5") (pinfunction "L-SI_5") (pintype "input"))
      (node (ref "LO") (pin "7") (pinfunction "GND_7") (pintype "power_in"))
      (node (ref "LO") (pin "8") (pinfunction "BI_8") (pintype "input"))
      (node (ref "OUT") (pin "K") (pinfunction "C_K") (pintype "passive"))
      (node (ref "PWR") (pin "K") (pinfunction "C_K") (pintype "passive"))
      (node (ref "S0") (pin "3") (pinfunction "S_3") (pintype "passive"))
      (node (ref "S1") (pin "3") (pinfunction "S_3") (pintype "passive"))
      (node (ref "S2") (pin "3") (pinfunction "S_3") (pintype "passive"))
      (node (ref "S3") (pin "3") (pinfunction "S_3") (pintype "passive"))
      (node (ref "S4") (pin "3") (pinfunction "S_3") (pintype "passive"))
      (node (ref "S5") (pin "3") (pinfunction "S_3") (pintype "passive"))
      (node (ref "S6") (pin "3") (pinfunction "S_3") (pintype "passive"))
      (node (ref "S7") (pin "3") (pinfunction "S_3") (pintype "passive"))
      (node (ref "TM1") (pin "3") (pinfunction "E_3") (pintype "passive"))
      (node (ref "X1") (pin "A1") (pinfunction "B_A1") (pintype "passive"))
      (node (ref "X1") (pin "A32") (pinfunction "B_A32") (pintype "passive"))
      (node (ref "X1") (pin "B1") (pinfunction "B_B1") (pintype "passive"))
      (node (ref "X1") (pin "B32") (pinfunction "B_B32") (pintype "passive"))
      (node (ref "X1") (pin "C1") (pinfunction "B_C1") (pintype "passive"))
      (node (ref "X1") (pin "C32") (pinfunction "B_C32") (pintype "passive"))
      (node (ref "X2") (pin "1") (pinfunction "VSS_1") (pintype "power_in"))
      (node (ref "X2") (pin "16") (pinfunction "K_16") (pintype "input"))
      (node (ref "X2") (pin "5") (pinfunction "RW_5") (pintype "input"))
      (node (ref "Y1") (pin "4") (pinfunction "GND_4") (pintype "power_in"))
    )
    (net (code "83") (name "ICLK") (class "Default")
      (node (ref "IC1") (pin "15") (pinfunction "BAUDOUT~{}_15") (pintype "output"))
      (node (ref "IC1") (pin "9") (pinfunction "RCLK_9") (pintype "input"))
    )
    (net (code "84") (name "IN") (class "Default")
      (node (ref "INPUT") (pin "1") (pinfunction "1_1") (pintype "passive"))
      (node (ref "X1") (pin "C26") (pinfunction "B_C26") (pintype "passive"))
    )
    (net (code "85") (name "IO-ADDR0") (class "Default")
      (node (ref "IC5") (pin "1") (pinfunction "A_1") (pintype "input"))
      (node (ref "X1") (pin "C7") (pinfunction "B_C7") (pintype "passive"))
    )
    (net (code "86") (name "IO-ADDR1") (class "Default")
      (node (ref "IC5") (pin "2") (pinfunction "B_2") (pintype "input"))
      (node (ref "X1") (pin "C8") (pinfunction "B_C8") (pintype "passive"))
    )
    (net (code "87") (name "IO-ADDR2") (class "Default")
      (node (ref "IC5") (pin "3") (pinfunction "C_3") (pintype "input"))
      (node (ref "X1") (pin "C9") (pinfunction "B_C9") (pintype "passive"))
    )
    (net (code "88") (name "IO-ADDR3") (class "Default")
      (node (ref "IO-ADDR-HL") (pin "2") (pinfunction "2_2") (pintype "passive"))
      (node (ref "IO-ADDR-HL") (pin "5") (pinfunction "5_5") (pintype "passive"))
      (node (ref "X1") (pin "C10") (pinfunction "B_C10") (pintype "passive"))
    )
    (net (code "89") (name "IO-RD") (class "Default")
      (node (ref "IC1") (pin "22") (pinfunction "IOR_22") (pintype "input"))
      (node (ref "IC6") (pin "3") (pinfunction "I0_3") (pintype "input"))
      (node (ref "IC8") (pin "2") (pinfunction "O_2") (pintype "open_collector"))
      (node (ref "RN2") (pin "7") (pinfunction "1_7") (pintype "passive"))
    )
    (net (code "90") (name "IO-SELDATA") (class "Default")
      (node (ref "IC1") (pin "12") (pinfunction "CS0_12") (pintype "input"))
      (node (ref "IC11") (pin "2") (pinfunction "I1_2") (pintype "input"))
      (node (ref "IC6") (pin "2") (pinfunction "I1_2") (pintype "input"))
      (node (ref "IC6") (pin "4") (pinfunction "I1_4") (pintype "input"))
      (node (ref "IC6") (pin "9") (pinfunction "I0_9") (pintype "input"))
      (node (ref "IC8") (pin "10") (pinfunction "O_10") (pintype "open_collector"))
      (node (ref "RN2") (pin "3") (pinfunction "1_3") (pintype "passive"))
    )
    (net (code "91") (name "IO-WR") (class "Default")
      (node (ref "IC1") (pin "19") (pinfunction "IOW_19") (pintype "input"))
      (node (ref "IC11") (pin "1") (pinfunction "I0_1") (pintype "input"))
      (node (ref "IC6") (pin "1") (pinfunction "I0_1") (pintype "input"))
      (node (ref "IC6") (pin "11") (pinfunction "I2_11") (pintype "input"))
      (node (ref "IC7") (pin "5") (pinfunction "I1_5") (pintype "input"))
      (node (ref "IC8") (pin "4") (pinfunction "O_4") (pintype "open_collector"))
      (node (ref "RN2") (pin "6") (pinfunction "1_6") (pintype "passive"))
    )
    (net (code "92") (name "LCD-ENABLE") (class "Default")
      (node (ref "IC10") (pin "5") (pinfunction "Q2_5") (pintype "output"))
      (node (ref "IC6") (pin "10") (pinfunction "I1_10") (pintype "input"))
    )
    (net (code "93") (name "LCD-REGISTER") (class "Default")
      (node (ref "IC10") (pin "6") (pinfunction "Q3_6") (pintype "output"))
      (node (ref "X2") (pin "4") (pinfunction "RS_4") (pintype "input"))
    )
    (net (code "94") (name "Net-(0-PadA)") (class "Default")
      (node (ref "0") (pin "A") (pinfunction "A_A") (pintype "passive"))
      (node (ref "R3") (pin "1") (pinfunction "1_1") (pintype "passive"))
    )
    (net (code "95") (name "Net-(1-PadA)") (class "Default")
      (node (ref "1") (pin "A") (pinfunction "A_A") (pintype "passive"))
      (node (ref "R4") (pin "1") (pinfunction "1_1") (pintype "passive"))
    )
    (net (code "96") (name "Net-(2-PadA)") (class "Default")
      (node (ref "2") (pin "A") (pinfunction "A_A") (pintype "passive"))
      (node (ref "R5") (pin "1") (pinfunction "1_1") (pintype "passive"))
    )
    (net (code "97") (name "Net-(3-PadA)") (class "Default")
      (node (ref "3") (pin "A") (pinfunction "A_A") (pintype "passive"))
      (node (ref "R6") (pin "1") (pinfunction "1_1") (pintype "passive"))
    )
    (net (code "98") (name "Net-(4-PadA)") (class "Default")
      (node (ref "4") (pin "A") (pinfunction "A_A") (pintype "passive"))
      (node (ref "R7") (pin "1") (pinfunction "1_1") (pintype "passive"))
    )
    (net (code "99") (name "Net-(5-PadA)") (class "Default")
      (node (ref "5") (pin "A") (pinfunction "A_A") (pintype "passive"))
      (node (ref "R8") (pin "1") (pinfunction "1_1") (pintype "passive"))
    )
    (net (code "100") (name "Net-(6-PadA)") (class "Default")
      (node (ref "6") (pin "A") (pinfunction "A_A") (pintype "passive"))
      (node (ref "R9") (pin "1") (pinfunction "1_1") (pintype "passive"))
    )
    (net (code "101") (name "Net-(7-PadA)") (class "Default")
      (node (ref "7") (pin "A") (pinfunction "A_A") (pintype "passive"))
      (node (ref "R10") (pin "1") (pinfunction "1_1") (pintype "passive"))
    )
    (net (code "102") (name "Net-(HIA-D0)") (class "Default")
      (node (ref "HI") (pin "3") (pinfunction "D0_3") (pintype "input"))
      (node (ref "IC9") (pin "12") (pinfunction "Q5_12") (pintype "output"))
    )
    (net (code "103") (name "Net-(HIA-D1)") (class "Default")
      (node (ref "HI") (pin "2") (pinfunction "D1_2") (pintype "input"))
      (node (ref "IC9") (pin "15") (pinfunction "Q6_15") (pintype "output"))
    )
    (net (code "104") (name "Net-(HIA-D2)") (class "Default")
      (node (ref "HI") (pin "13") (pinfunction "D2_13") (pintype "input"))
      (node (ref "IC9") (pin "16") (pinfunction "Q7_16") (pintype "output"))
    )
    (net (code "105") (name "Net-(HIA-D3)") (class "Default")
      (node (ref "HI") (pin "12") (pinfunction "D3_12") (pintype "input"))
      (node (ref "IC9") (pin "19") (pinfunction "Q8_19") (pintype "output"))
    )
    (net (code "106") (name "Net-(IC1A-INT)") (class "Default")
      (node (ref "IC1") (pin "30") (pinfunction "INT_30") (pintype "output"))
      (node (ref "INT") (pin "1") (pinfunction "1_1") (pintype "passive"))
    )
    (net (code "107") (name "Net-(IC1A-TX)") (class "Default")
      (node (ref "IC1") (pin "11") (pinfunction "TX_11") (pintype "output"))
      (node (ref "IC2") (pin "11") (pinfunction "T1IN_11") (pintype "input"))
    )
    (net (code "108") (name "Net-(IC1A-XTAL1)") (class "Default")
      (node (ref "IC1") (pin "16") (pinfunction "XTAL1_16") (pintype "input"))
      (node (ref "Y1") (pin "5") (pinfunction "OUTPUT_5") (pintype "output"))
    )
    (net (code "109") (name "Net-(IC2A-C1+)") (class "Default")
      (node (ref "C1") (pin "+") (pinfunction "+_+") (pintype "passive"))
      (node (ref "IC2") (pin "1") (pinfunction "C1+_1") (pintype "bidirectional"))
    )
    (net (code "110") (name "Net-(IC2A-C1-)") (class "Default")
      (node (ref "C1") (pin "-") (pinfunction "-_-") (pintype "passive"))
      (node (ref "IC2") (pin "3") (pinfunction "C1-_3") (pintype "bidirectional"))
    )
    (net (code "111") (name "Net-(IC2A-C2+)") (class "Default")
      (node (ref "C2") (pin "+") (pinfunction "+_+") (pintype "passive"))
      (node (ref "IC2") (pin "4") (pinfunction "C2+_4") (pintype "bidirectional"))
    )
    (net (code "112") (name "Net-(IC2A-C2-)") (class "Default")
      (node (ref "C2") (pin "-") (pinfunction "-_-") (pintype "passive"))
      (node (ref "IC2") (pin "5") (pinfunction "C2-_5") (pintype "bidirectional"))
    )
    (net (code "113") (name "Net-(IC2A-V+)") (class "Default")
      (node (ref "C3") (pin "+") (pinfunction "+_+") (pintype "passive"))
      (node (ref "IC2") (pin "2") (pinfunction "V+_2") (pintype "bidirectional"))
    )
    (net (code "114") (name "Net-(IC2A-V-)") (class "Default")
      (node (ref "C4") (pin "-") (pinfunction "-_-") (pintype "passive"))
      (node (ref "IC2") (pin "6") (pinfunction "V-_6") (pintype "bidirectional"))
    )
    (net (code "115") (name "Net-(IC3A-A1)") (class "Default")
      (node (ref "IC3") (pin "2") (pinfunction "A1_2") (pintype "input"))
      (node (ref "S0") (pin "2") (pinfunction "P_2") (pintype "passive"))
    )
    (net (code "116") (name "Net-(IC3A-A2)") (class "Default")
      (node (ref "IC3") (pin "4") (pinfunction "A2_4") (pintype "input"))
      (node (ref "S1") (pin "2") (pinfunction "P_2") (pintype "passive"))
    )
    (net (code "117") (name "Net-(IC3A-A3)") (class "Default")
      (node (ref "IC3") (pin "6") (pinfunction "A3_6") (pintype "input"))
      (node (ref "S2") (pin "2") (pinfunction "P_2") (pintype "passive"))
    )
    (net (code "118") (name "Net-(IC3A-A4)") (class "Default")
      (node (ref "IC3") (pin "8") (pinfunction "A4_8") (pintype "input"))
      (node (ref "S3") (pin "2") (pinfunction "P_2") (pintype "passive"))
    )
    (net (code "119") (name "Net-(IC3A-G)") (class "Default")
      (node (ref "IC3") (pin "1") (pinfunction "G_1") (pintype "input"))
      (node (ref "IC3") (pin "19") (pinfunction "G_19") (pintype "input"))
      (node (ref "IC6") (pin "6") (pinfunction "O_6") (pintype "output"))
    )
    (net (code "120") (name "Net-(IC3B-A1)") (class "Default")
      (node (ref "IC3") (pin "11") (pinfunction "A1_11") (pintype "input"))
      (node (ref "S4") (pin "2") (pinfunction "P_2") (pintype "passive"))
    )
    (net (code "121") (name "Net-(IC3B-A2)") (class "Default")
      (node (ref "IC3") (pin "13") (pinfunction "A2_13") (pintype "input"))
      (node (ref "S5") (pin "2") (pinfunction "P_2") (pintype "passive"))
    )
    (net (code "122") (name "Net-(IC3B-A3)") (class "Default")
      (node (ref "IC3") (pin "15") (pinfunction "A3_15") (pintype "input"))
      (node (ref "S6") (pin "2") (pinfunction "P_2") (pintype "passive"))
    )
    (net (code "123") (name "Net-(IC3B-A4)") (class "Default")
      (node (ref "IC3") (pin "17") (pinfunction "A4_17") (pintype "input"))
      (node (ref "S7") (pin "2") (pinfunction "P_2") (pintype "passive"))
    )
    (net (code "124") (name "Net-(IC4A-CLK)") (class "Default")
      (node (ref "IC4") (pin "11") (pinfunction "CLK_11") (pintype "input"))
      (node (ref "IC6") (pin "12") (pinfunction "O_12") (pintype "output"))
    )
    (net (code "125") (name "Net-(IC4A-Q1)") (class "Default")
      (node (ref "IC4") (pin "2") (pinfunction "Q1_2") (pintype "output"))
      (node (ref "R3") (pin "2") (pinfunction "2_2") (pintype "passive"))
    )
    (net (code "126") (name "Net-(IC4A-Q2)") (class "Default")
      (node (ref "IC4") (pin "5") (pinfunction "Q2_5") (pintype "output"))
      (node (ref "R4") (pin "2") (pinfunction "2_2") (pintype "passive"))
    )
    (net (code "127") (name "Net-(IC4A-Q3)") (class "Default")
      (node (ref "IC4") (pin "6") (pinfunction "Q3_6") (pintype "output"))
      (node (ref "R5") (pin "2") (pinfunction "2_2") (pintype "passive"))
    )
    (net (code "128") (name "Net-(IC4A-Q4)") (class "Default")
      (node (ref "IC4") (pin "9") (pinfunction "Q4_9") (pintype "output"))
      (node (ref "R6") (pin "2") (pinfunction "2_2") (pintype "passive"))
    )
    (net (code "129") (name "Net-(IC4A-Q5)") (class "Default")
      (node (ref "IC4") (pin "12") (pinfunction "Q5_12") (pintype "output"))
      (node (ref "R7") (pin "2") (pinfunction "2_2") (pintype "passive"))
    )
    (net (code "130") (name "Net-(IC4A-Q6)") (class "Default")
      (node (ref "IC4") (pin "15") (pinfunction "Q6_15") (pintype "output"))
      (node (ref "R8") (pin "2") (pinfunction "2_2") (pintype "passive"))
    )
    (net (code "131") (name "Net-(IC4A-Q7)") (class "Default")
      (node (ref "IC4") (pin "16") (pinfunction "Q7_16") (pintype "output"))
      (node (ref "R9") (pin "2") (pinfunction "2_2") (pintype "passive"))
    )
    (net (code "132") (name "Net-(IC4A-Q8)") (class "Default")
      (node (ref "IC4") (pin "19") (pinfunction "Q8_19") (pintype "output"))
      (node (ref "R10") (pin "2") (pinfunction "2_2") (pintype "passive"))
    )
    (net (code "133") (name "Net-(IC5A-G1)") (class "Default")
      (node (ref "IC5") (pin "6") (pinfunction "G1_6") (pintype "input"))
      (node (ref "IO-ADDR-HL") (pin "4") (pinfunction "4_4") (pintype "passive"))
    )
    (net (code "134") (name "Net-(IC5A-G2A)") (class "Default")
      (node (ref "IC5") (pin "4") (pinfunction "G2A_4") (pintype "input"))
      (node (ref "IO-ADDR-HL") (pin "3") (pinfunction "3_3") (pintype "passive"))
    )
    (net (code "135") (name "Net-(IC6C-O)") (class "Default")
      (node (ref "IC6") (pin "8") (pinfunction "O_8") (pintype "output"))
      (node (ref "IC7") (pin "1") (pinfunction "I0_1") (pintype "input"))
      (node (ref "IC7") (pin "2") (pinfunction "I1_2") (pintype "input"))
    )
    (net (code "136") (name "Net-(IC7A-O)") (class "Default")
      (node (ref "IC7") (pin "3") (pinfunction "O_3") (pintype "output"))
      (node (ref "X2") (pin "6") (pinfunction "E_6") (pintype "input"))
    )
    (net (code "137") (name "Net-(IC7B-I0)") (class "Default")
      (node (ref "IC7") (pin "11") (pinfunction "O_11") (pintype "output"))
      (node (ref "IC7") (pin "4") (pinfunction "I0_4") (pintype "input"))
    )
    (net (code "138") (name "Net-(IC8F-I)") (class "Default")
      (node (ref "IC8") (pin "13") (pinfunction "I_13") (pintype "input"))
      (node (ref "INT") (pin "2") (pinfunction "2_2") (pintype "passive"))
    )
    (net (code "139") (name "Net-(IC9A-Q1)") (class "Default")
      (node (ref "IC9") (pin "2") (pinfunction "Q1_2") (pintype "output"))
      (node (ref "LO") (pin "3") (pinfunction "D0_3") (pintype "input"))
    )
    (net (code "140") (name "Net-(IC9A-Q2)") (class "Default")
      (node (ref "IC9") (pin "5") (pinfunction "Q2_5") (pintype "output"))
      (node (ref "LO") (pin "2") (pinfunction "D1_2") (pintype "input"))
    )
    (net (code "141") (name "Net-(IC9A-Q3)") (class "Default")
      (node (ref "IC9") (pin "6") (pinfunction "Q3_6") (pintype "output"))
      (node (ref "LO") (pin "13") (pinfunction "D2_13") (pintype "input"))
    )
    (net (code "142") (name "Net-(IC9A-Q4)") (class "Default")
      (node (ref "IC9") (pin "9") (pinfunction "Q4_9") (pintype "output"))
      (node (ref "LO") (pin "12") (pinfunction "D3_12") (pintype "input"))
    )
    (net (code "143") (name "Net-(IC10A-CLK)") (class "Default")
      (node (ref "IC10") (pin "11") (pinfunction "CLK_11") (pintype "input"))
      (node (ref "IC7") (pin "6") (pinfunction "O_6") (pintype "output"))
    )
    (net (code "144") (name "Net-(IC11A-O)") (class "Default")
      (node (ref "IC11") (pin "12") (pinfunction "O_12") (pintype "output"))
      (node (ref "IC9") (pin "11") (pinfunction "CLK_11") (pintype "input"))
    )
    (net (code "145") (name "Net-(IN-P)") (class "Default")
      (node (ref "IN") (pin "2") (pinfunction "P_2") (pintype "passive"))
      (node (ref "INPUT") (pin "2") (pinfunction "2_2") (pintype "passive"))
    )
    (net (code "146") (name "Net-(J1-Pad2)") (class "Default")
      (node (ref "J1") (pin "2") (pinfunction "2_2") (pintype "passive"))
      (node (ref "JP1") (pin "4") (pinfunction "4_4") (pintype "passive"))
    )
    (net (code "147") (name "Net-(J1-Pad3)") (class "Default")
      (node (ref "J1") (pin "3") (pinfunction "3_3") (pintype "passive"))
      (node (ref "JP1") (pin "3") (pinfunction "3_3") (pintype "passive"))
    )
    (net (code "148") (name "Net-(OUT-PadA)") (class "Default")
      (node (ref "OUT") (pin "A") (pinfunction "A_A") (pintype "passive"))
      (node (ref "R1") (pin "1") (pinfunction "1_1") (pintype "passive"))
    )
    (net (code "149") (name "Net-(PWR-PadA)") (class "Default")
      (node (ref "PWR") (pin "A") (pinfunction "A_A") (pintype "passive"))
      (node (ref "R2") (pin "1") (pinfunction "1_1") (pintype "passive"))
    )
    (net (code "150") (name "Net-(TM1-S)") (class "Default")
      (node (ref "TM1") (pin "2") (pinfunction "S_2") (pintype "passive"))
      (node (ref "X2") (pin "3") (pinfunction "VO_3") (pintype "input"))
    )
    (net (code "151") (name "OUT") (class "Default")
      (node (ref "R1") (pin "2") (pinfunction "2_2") (pintype "passive"))
      (node (ref "X1") (pin "C27") (pinfunction "B_C27") (pintype "passive"))
    )
    (net (code "152") (name "REG-LD-ID0") (class "Default")
      (node (ref "X1") (pin "B13") (pinfunction "B_B13") (pintype "passive"))
    )
    (net (code "153") (name "REG-LD-ID1") (class "Default")
      (node (ref "X1") (pin "B14") (pinfunction "B_B14") (pintype "passive"))
    )
    (net (code "154") (name "REG-LD-ID2") (class "Default")
      (node (ref "X1") (pin "B15") (pinfunction "B_B15") (pintype "passive"))
    )
    (net (code "155") (name "REG-LD-ID3") (class "Default")
      (node (ref "X1") (pin "B16") (pinfunction "B_B16") (pintype "passive"))
    )
    (net (code "156") (name "REG-RD-ID0") (class "Default")
      (node (ref "X1") (pin "B9") (pinfunction "B_B9") (pintype "passive"))
    )
    (net (code "157") (name "REG-RD-ID1") (class "Default")
      (node (ref "X1") (pin "B10") (pinfunction "B_B10") (pintype "passive"))
    )
    (net (code "158") (name "REG-RD-ID2") (class "Default")
      (node (ref "X1") (pin "B11") (pinfunction "B_B11") (pintype "passive"))
    )
    (net (code "159") (name "REG-RD-ID3") (class "Default")
      (node (ref "X1") (pin "B12") (pinfunction "B_B12") (pintype "passive"))
    )
    (net (code "160") (name "RESET") (class "Default")
      (node (ref "IC1") (pin "35") (pinfunction "RESET_35") (pintype "input"))
      (node (ref "IC8") (pin "6") (pinfunction "O_6") (pintype "open_collector"))
      (node (ref "IC8") (pin "9") (pinfunction "I_9") (pintype "input"))
      (node (ref "RN2") (pin "5") (pinfunction "1_5") (pintype "passive"))
    )
    (net (code "161") (name "RX") (class "Default")
      (node (ref "IC1") (pin "10") (pinfunction "RX_10") (pintype "input"))
      (node (ref "IC2") (pin "12") (pinfunction "R1OUT_12") (pintype "output"))
    )
    (net (code "162") (name "RX-IN") (class "Default")
      (node (ref "IC2") (pin "13") (pinfunction "R1IN_13") (pintype "input"))
      (node (ref "JP1") (pin "1") (pinfunction "1_1") (pintype "passive"))
      (node (ref "JP1") (pin "6") (pinfunction "6_6") (pintype "passive"))
    )
    (net (code "163") (name "SWITCH-LED") (class "Default")
      (node (ref "IC10") (pin "2") (pinfunction "Q1_2") (pintype "output"))
      (node (ref "IC6") (pin "13") (pinfunction "I2_13") (pintype "input"))
      (node (ref "IC6") (pin "5") (pinfunction "I2_5") (pintype "input"))
    )
    (net (code "164") (name "TIL311") (class "Default")
      (node (ref "IC10") (pin "19") (pinfunction "Q8_19") (pintype "output"))
      (node (ref "IC11") (pin "13") (pinfunction "I2_13") (pintype "input"))
    )
    (net (code "165") (name "TX-OUT") (class "Default")
      (node (ref "IC2") (pin "14") (pinfunction "T1OUT_14") (pintype "output"))
      (node (ref "JP1") (pin "2") (pinfunction "2_2") (pintype "passive"))
      (node (ref "JP1") (pin "5") (pinfunction "5_5") (pintype "passive"))
    )
    (net (code "166") (name "UART-A0") (class "Default")
      (node (ref "IC1") (pin "28") (pinfunction "A0_28") (pintype "input"))
      (node (ref "IC10") (pin "9") (pinfunction "Q4_9") (pintype "output"))
    )
    (net (code "167") (name "UART-A1") (class "Default")
      (node (ref "IC1") (pin "27") (pinfunction "A1_27") (pintype "input"))
      (node (ref "IC10") (pin "12") (pinfunction "Q5_12") (pintype "output"))
    )
    (net (code "168") (name "UART-A2") (class "Default")
      (node (ref "IC1") (pin "26") (pinfunction "A2_26") (pintype "input"))
      (node (ref "IC10") (pin "15") (pinfunction "Q6_15") (pintype "output"))
    )
    (net (code "169") (name "UART-CS") (class "Default")
      (node (ref "IC1") (pin "13") (pinfunction "CS1_13") (pintype "input"))
      (node (ref "IC10") (pin "16") (pinfunction "Q7_16") (pintype "output"))
    )
    (net (code "170") (name "VCC") (class "Default")
      (node (ref "C10") (pin "1") (pinfunction "1_1") (pintype "passive"))
      (node (ref "C11") (pin "1") (pinfunction "1_1") (pintype "passive"))
      (node (ref "C12") (pin "1") (pinfunction "1_1") (pintype "passive"))
      (node (ref "C13") (pin "1") (pinfunction "1_1") (pintype "passive"))
      (node (ref "C14") (pin "1") (pinfunction "1_1") (pintype "passive"))
      (node (ref "C15") (pin "1") (pinfunction "1_1") (pintype "passive"))
      (node (ref "C16") (pin "1") (pinfunction "1_1") (pintype "passive"))
      (node (ref "C17") (pin "1") (pinfunction "1_1") (pintype "passive"))
      (node (ref "C3") (pin "-") (pinfunction "-_-") (pintype "passive"))
      (node (ref "C5") (pin "1") (pinfunction "1_1") (pintype "passive"))
      (node (ref "C6") (pin "1") (pinfunction "1_1") (pintype "passive"))
      (node (ref "C7") (pin "1") (pinfunction "1_1") (pintype "passive"))
      (node (ref "C8") (pin "1") (pinfunction "1_1") (pintype "passive"))
      (node (ref "C9") (pin "1") (pinfunction "1_1") (pintype "passive"))
      (node (ref "HI") (pin "1") (pinfunction "LEDSUP_1") (pintype "input"))
      (node (ref "HI") (pin "14") (pinfunction "VCC_14") (pintype "power_in"))
      (node (ref "IC1") (pin "18") (pinfunction "IOW~{}_18") (pintype "input"))
      (node (ref "IC1") (pin "21") (pinfunction "IOR~{}_21") (pintype "input"))
      (node (ref "IC1") (pin "36") (pinfunction "CTS~{}_36") (pintype "input"))
      (node (ref "IC1") (pin "37") (pinfunction "DSR~{}_37") (pintype "input"))
      (node (ref "IC1") (pin "38") (pinfunction "CD~{}_38") (pintype "input"))
      (node (ref "IC1") (pin "39") (pinfunction "RI~{}_39") (pintype "input"))
      (node (ref "IN") (pin "1") (pinfunction "O_1") (pintype "passive"))
      (node (ref "IO-ADDR-HL") (pin "6") (pinfunction "6_6") (pintype "passive"))
      (node (ref "LO") (pin "1") (pinfunction "LEDSUP_1") (pintype "input"))
      (node (ref "LO") (pin "14") (pinfunction "VCC_14") (pintype "power_in"))
      (node (ref "R2") (pin "2") (pinfunction "2_2") (pintype "passive"))
      (node (ref "RN2") (pin "1") (pinfunction "1_1") (pintype "passive"))
      (node (ref "S0") (pin "1") (pinfunction "O_1") (pintype "passive"))
      (node (ref "S1") (pin "1") (pinfunction "O_1") (pintype "passive"))
      (node (ref "S2") (pin "1") (pinfunction "O_1") (pintype "passive"))
      (node (ref "S3") (pin "1") (pinfunction "O_1") (pintype "passive"))
      (node (ref "S4") (pin "1") (pinfunction "O_1") (pintype "passive"))
      (node (ref "S5") (pin "1") (pinfunction "O_1") (pintype "passive"))
      (node (ref "S6") (pin "1") (pinfunction "O_1") (pintype "passive"))
      (node (ref "S7") (pin "1") (pinfunction "O_1") (pintype "passive"))
      (node (ref "TM1") (pin "1") (pinfunction "A_1") (pintype "passive"))
      (node (ref "X1") (pin "A2") (pinfunction "B_A2") (pintype "passive"))
      (node (ref "X1") (pin "A31") (pinfunction "B_A31") (pintype "passive"))
      (node (ref "X1") (pin "B2") (pinfunction "B_B2") (pintype "passive"))
      (node (ref "X1") (pin "B31") (pinfunction "B_B31") (pintype "passive"))
      (node (ref "X1") (pin "C2") (pinfunction "B_C2") (pintype "passive"))
      (node (ref "X1") (pin "C31") (pinfunction "B_C31") (pintype "passive"))
      (node (ref "X2") (pin "15") (pinfunction "A_15") (pintype "input"))
      (node (ref "X2") (pin "2") (pinfunction "VDD_2") (pintype "power_in"))
      (node (ref "Y1") (pin "8") (pinfunction "+5VDC_8") (pintype "input"))
    )
    (net (code "171") (name "unconnected-(HIA-DP-L-Pad4)") (class "Default")
      (node (ref "HI") (pin "4") (pinfunction "DP-L_4") (pintype "input"))
    )
    (net (code "172") (name "unconnected-(HIA-DP-R-Pad10)") (class "Default")
      (node (ref "HI") (pin "10") (pinfunction "DP-R_10") (pintype "input"))
    )
    (net (code "173") (name "unconnected-(IC1A-DDIS~{}-Pad23)") (class "Default")
      (node (ref "IC1") (pin "23") (pinfunction "DDIS~{}_23") (pintype "output"))
    )
    (net (code "174") (name "unconnected-(IC1A-DTR~{}-Pad33)") (class "Default")
      (node (ref "IC1") (pin "33") (pinfunction "DTR~{}_33") (pintype "output"))
    )
    (net (code "175") (name "unconnected-(IC1A-OP1~{}-Pad34)") (class "Default")
      (node (ref "IC1") (pin "34") (pinfunction "OP1~{}_34") (pintype "output"))
    )
    (net (code "176") (name "unconnected-(IC1A-OP2~{}-Pad31)") (class "Default")
      (node (ref "IC1") (pin "31") (pinfunction "OP2~{}_31") (pintype "output"))
    )
    (net (code "177") (name "unconnected-(IC1A-RTS~{}-Pad32)") (class "Default")
      (node (ref "IC1") (pin "32") (pinfunction "RTS~{}_32") (pintype "output"))
    )
    (net (code "178") (name "unconnected-(IC1A-RXRDY~{}-Pad29)") (class "Default")
      (node (ref "IC1") (pin "29") (pinfunction "RXRDY~{}_29") (pintype "output"))
    )
    (net (code "179") (name "unconnected-(IC1A-TXRDY~{}-Pad24)") (class "Default")
      (node (ref "IC1") (pin "24") (pinfunction "TXRDY~{}_24") (pintype "output"))
    )
    (net (code "180") (name "unconnected-(IC1A-XTAL2-Pad17)") (class "Default")
      (node (ref "IC1") (pin "17") (pinfunction "XTAL2_17") (pintype "input"))
    )
    (net (code "181") (name "unconnected-(IC2A-R2IN-Pad8)") (class "Default")
      (node (ref "IC2") (pin "8") (pinfunction "R2IN_8") (pintype "input"))
    )
    (net (code "182") (name "unconnected-(IC2A-R2OUT-Pad9)") (class "Default")
      (node (ref "IC2") (pin "9") (pinfunction "R2OUT_9") (pintype "output"))
    )
    (net (code "183") (name "unconnected-(IC2A-T2IN-Pad10)") (class "Default")
      (node (ref "IC2") (pin "10") (pinfunction "T2IN_10") (pintype "input"))
    )
    (net (code "184") (name "unconnected-(IC2A-T2OUT-Pad7)") (class "Default")
      (node (ref "IC2") (pin "7") (pinfunction "T2OUT_7") (pintype "output"))
    )
    (net (code "185") (name "unconnected-(IC7C-O-Pad8)") (class "Default")
      (node (ref "IC7") (pin "8") (pinfunction "O_8") (pintype "output"))
    )
    (net (code "186") (name "unconnected-(IC11B-O-Pad6)") (class "Default")
      (node (ref "IC11") (pin "6") (pinfunction "O_6") (pintype "output"))
    )
    (net (code "187") (name "unconnected-(IC11C-O-Pad8)") (class "Default")
      (node (ref "IC11") (pin "8") (pinfunction "O_8") (pintype "output"))
    )
    (net (code "188") (name "unconnected-(J1-Pad1)") (class "Default")
      (node (ref "J1") (pin "1") (pinfunction "1_1") (pintype "passive"))
    )
    (net (code "189") (name "unconnected-(J1-Pad4)") (class "Default")
      (node (ref "J1") (pin "4") (pinfunction "4_4") (pintype "passive"))
    )
    (net (code "190") (name "unconnected-(J1-Pad6)") (class "Default")
      (node (ref "J1") (pin "6") (pinfunction "6_6") (pintype "passive"))
    )
    (net (code "191") (name "unconnected-(J1-Pad7)") (class "Default")
      (node (ref "J1") (pin "7") (pinfunction "7_7") (pintype "passive"))
    )
    (net (code "192") (name "unconnected-(J1-Pad8)") (class "Default")
      (node (ref "J1") (pin "8") (pinfunction "8_8") (pintype "passive"))
    )
    (net (code "193") (name "unconnected-(J1-Pad9)") (class "Default")
      (node (ref "J1") (pin "9") (pinfunction "9_9") (pintype "passive"))
    )
    (net (code "194") (name "unconnected-(LOA-DP-L-Pad4)") (class "Default")
      (node (ref "LO") (pin "4") (pinfunction "DP-L_4") (pintype "input"))
    )
    (net (code "195") (name "unconnected-(LOA-DP-R-Pad10)") (class "Default")
      (node (ref "LO") (pin "10") (pinfunction "DP-R_10") (pintype "input"))
    )
  )
)
